# Sheet1.net
KiCad netlist of a schematic drawn in Altium Designer
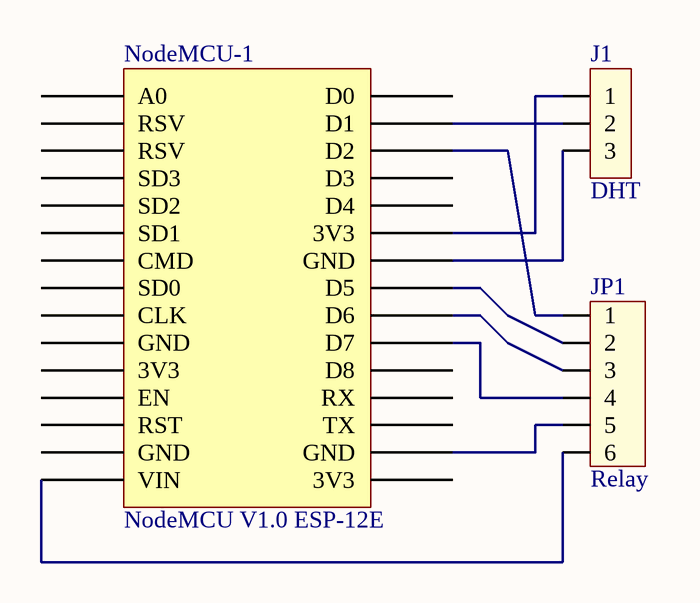
[diagram p0: Sheet1.SchDoc]

(export (version "E")
  (design (tool "Eeschema 10.0.6"))
  (components
    (comp (ref "J1")
      (value "DHT")
      (footprint "JP3")
      (description "Jumper 3")
      (libsource (lib "PART") (part "JP3"))
    )
    (comp (ref "JP1")
      (value "Relay")
      (footprint "CON6")
      (description "Connector 6")
      (libsource (lib "PART") (part "Con6"))
    )
    (comp (ref "NodeMCU-1")
      (value "NodeMCU V1.0 ESP-12E")
      (footprint "NodeMCU V1.0 ESP-12E")
      (description "NodeMCU V1.0 ESP8266 (ESP-12E)")
      (libsource (lib "nodemcu") (part "NodeMCU V1.0 ESP-12E"))
    )
  )
  (nets
    (net (code "1") (name "Net-(J1-Pad1)") (class "Default")
      (node (ref "J1") (pin "1") (pinfunction "1_1") (pintype "passive"))
      (node (ref "NodeMCU-1") (pin "3V3") (pinfunction "3V3_3V3") (pintype "passive"))
    )
    (net (code "2") (name "Net-(J1-Pad2)") (class "Default")
      (node (ref "J1") (pin "2") (pinfunction "2_2") (pintype "passive"))
      (node (ref "NodeMCU-1") (pin "D1") (pinfunction "D1_D1") (pintype "passive"))
    )
    (net (code "3") (name "Net-(J1-Pad3)") (class "Default")
      (node (ref "J1") (pin "3") (pinfunction "3_3") (pintype "passive"))
      (node (ref "NodeMCU-1") (pin "GND") (pinfunction "GND_GND") (pintype "passive"))
    )
    (net (code "4") (name "Net-(JP1-Pad1)") (class "Default")
      (node (ref "JP1") (pin "1") (pinfunction "1_1") (pintype "passive"))
      (node (ref "NodeMCU-1") (pin "D2") (pinfunction "D2_D2") (pintype "passive"))
    )
    (net (code "5") (name "Net-(JP1-Pad2)") (class "Default")
      (node (ref "JP1") (pin "2") (pinfunction "2_2") (pintype "passive"))
      (node (ref "NodeMCU-1") (pin "D5") (pinfunction "D5_D5") (pintype "passive"))
    )
    (net (code "6") (name "Net-(JP1-Pad3)") (class "Default")
      (node (ref "JP1") (pin "3") (pinfunction "3_3") (pintype "passive"))
      (node (ref "NodeMCU-1") (pin "D6") (pinfunction "D6_D6") (pintype "passive"))
    )
    (net (code "7") (name "Net-(JP1-Pad4)") (class "Default")
      (node (ref "JP1") (pin "4") (pinfunction "4_4") (pintype "passive"))
      (node (ref "NodeMCU-1") (pin "D7") (pinfunction "D7_D7") (pintype "passive"))
    )
    (net (code "8") (name "Net-(JP1-Pad5)") (class "Default")
      (node (ref "JP1") (pin "5") (pinfunction "5_5") (pintype "passive"))
      (node (ref "NodeMCU-1") (pin "GND") (pinfunction "GND_GND") (pintype "passive"))
    )
    (net (code "9") (name "Net-(JP1-Pad6)") (class "Default")
      (node (ref "JP1") (pin "6") (pinfunction "6_6") (pintype "passive"))
      (node (ref "NodeMCU-1") (pin "VIN") (pinfunction "VIN_VIN") (pintype "passive"))
    )
    (net (code "10") (name "unconnected-(NodeMCU-1-Pad3V3)") (class "Default")
      (node (ref "NodeMCU-1") (pin "3V3") (pinfunction "3V3_3V3") (pintype "passive"))
    )
    (net (code "11") (name "unconnected-(NodeMCU-1-Pad3V3)_1") (class "Default")
      (node (ref "NodeMCU-1") (pin "3V3") (pinfunction "3V3_3V3") (pintype "passive"))
    )
    (net (code "12") (name "unconnected-(NodeMCU-1-PadA0)") (class "Default")
      (node (ref "NodeMCU-1") (pin "A0") (pinfunction "A0_A0") (pintype "passive"))
    )
    (net (code "13") (name "unconnected-(NodeMCU-1-PadCLK)") (class "Default")
      (node (ref "NodeMCU-1") (pin "CLK") (pinfunction "CLK_CLK") (pintype "passive"))
    )
    (net (code "14") (name "unconnected-(NodeMCU-1-PadCMD)") (class "Default")
      (node (ref "NodeMCU-1") (pin "CMD") (pinfunction "CMD_CMD") (pintype "passive"))
    )
    (net (code "15") (name "unconnected-(NodeMCU-1-PadD0)") (class "Default")
      (node (ref "NodeMCU-1") (pin "D0") (pinfunction "D0_D0") (pintype "passive"))
    )
    (net (code "16") (name "unconnected-(NodeMCU-1-PadD3)") (class "Default")
      (node (ref "NodeMCU-1") (pin "D3") (pinfunction "D3_D3") (pintype "passive"))
    )
    (net (code "17") (name "unconnected-(NodeMCU-1-PadD4)") (class "Default")
      (node (ref "NodeMCU-1") (pin "D4") (pinfunction "D4_D4") (pintype "passive"))
    )
    (net (code "18") (name "unconnected-(NodeMCU-1-PadD8)") (class "Default")
      (node (ref "NodeMCU-1") (pin "D8") (pinfunction "D8_D8") (pintype "passive"))
    )
    (net (code "19") (name "unconnected-(NodeMCU-1-PadEN)") (class "Default")
      (node (ref "NodeMCU-1") (pin "EN") (pinfunction "EN_EN") (pintype "passive"))
    )
    (net (code "20") (name "unconnected-(NodeMCU-1-PadGND)") (class "Default")
      (node (ref "NodeMCU-1") (pin "GND") (pinfunction "GND_GND") (pintype "passive"))
    )
    (net (code "21") (name "unconnected-(NodeMCU-1-PadGND)_1") (class "Default")
      (node (ref "NodeMCU-1") (pin "GND") (pinfunction "GND_GND") (pintype "passive"))
    )
    (net (code "22") (name "unconnected-(NodeMCU-1-PadRST)") (class "Default")
      (node (ref "NodeMCU-1") (pin "RST") (pinfunction "RST_RST") (pintype "passive"))
    )
    (net (code "23") (name "unconnected-(NodeMCU-1-PadRSV)") (class "Default")
      (node (ref "NodeMCU-1") (pin "RSV") (pinfunction "RSV_RSV") (pintype "passive"))
    )
    (net (code "24") (name "unconnected-(NodeMCU-1-PadRSV)_1") (class "Default")
      (node (ref "NodeMCU-1") (pin "RSV") (pinfunction "RSV_RSV") (pintype "passive"))
    )
    (net (code "25") (name "unconnected-(NodeMCU-1-PadRX)") (class "Default")
      (node (ref "NodeMCU-1") (pin "RX") (pinfunction "RX_RX") (pintype "passive"))
    )
    (net (code "26") (name "unconnected-(NodeMCU-1-PadSD0)") (class "Default")
      (node (ref "NodeMCU-1") (pin "SD0") (pinfunction "SD0_SD0") (pintype "passive"))
    )
    (net (code "27") (name "unconnected-(NodeMCU-1-PadSD1)") (class "Default")
      (node (ref "NodeMCU-1") (pin "SD1") (pinfunction "SD1_SD1") (pintype "passive"))
    )
    (net (code "28") (name "unconnected-(NodeMCU-1-PadSD2)") (class "Default")
      (node (ref "NodeMCU-1") (pin "SD2") (pinfunction "SD2_SD2") (pintype "passive"))
    )
    (net (code "29") (name "unconnected-(NodeMCU-1-PadSD3)") (class "Default")
      (node (ref "NodeMCU-1") (pin "SD3") (pinfunction "SD3_SD3") (pintype "passive"))
    )
    (net (code "30") (name "unconnected-(NodeMCU-1-PadTX)") (class "Default")
      (node (ref "NodeMCU-1") (pin "TX") (pinfunction "TX_TX") (pintype "passive"))
    )
  )
)
